# RF.net
KiCad netlist of a schematic drawn in Altium Designer
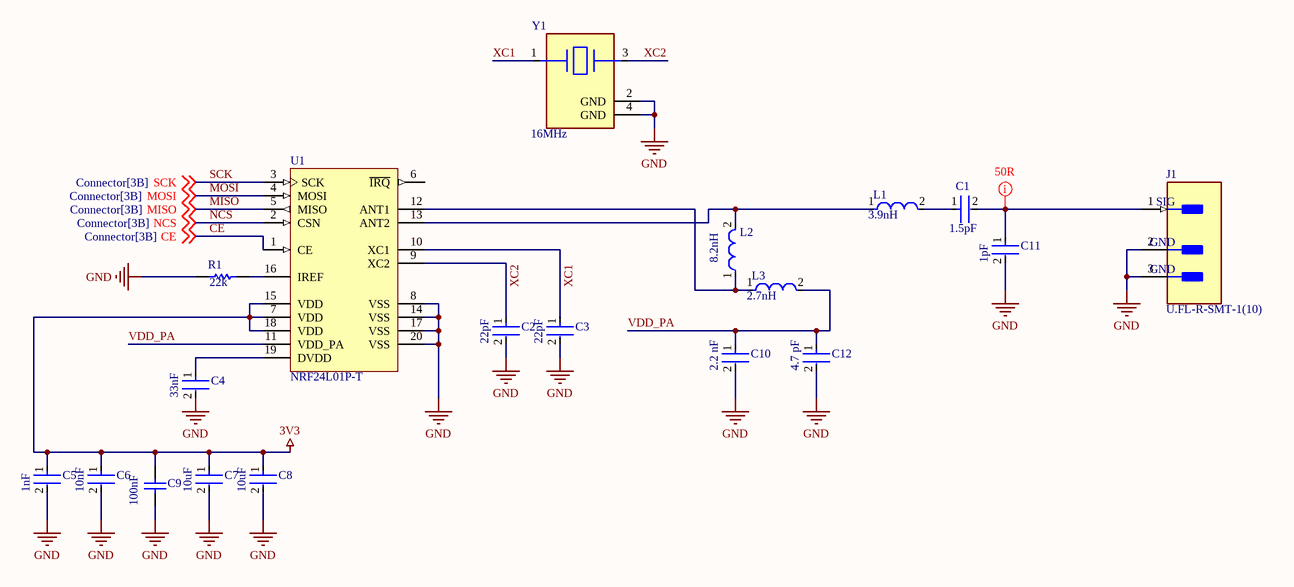
[diagram p0: RF.SchDoc]

(export (version "E")
  (design (tool "Eeschema 10.0.6"))
  (components
    (comp (ref "C1")
      (value "GCM1555C1H1R5BA16D")
      (footprint "FP-GCM155-0_05-IPC_C")
      (description "Ceramic Capacitor for Automotive 1.5pF ±0.1pF 50VDC C0G 0402 Paper T/R")
      (fields (field (name "CAPACITANCE") "1.5pF") (field (name "JLCPARTNUM") "C126500"))
      (libsource (lib "Altium Content Vault") (part "02cd4be3c70576c341d710602a673aa"))
    )
    (comp (ref "C2")
      (value "04025A220JAT2A")
      (footprint "FP-0402-L_1_0_1-W_0_5_0_1-MFG")
      (description "General Purpose Ceramic Capacitor, 0402, 22pF, 5%, C0G, 30ppm/°C, 50V")
      (fields
        (field (name "VOLTAGE") "50V")
        (field (name "TOLERANCE") "5%")
        (field (name "CAPACITANCE") "22pF")
      )
      (libsource (lib "Altium Content Vault") (part "b4654b650e69147ec39a6b967a45e02"))
    )
    (comp (ref "C3")
      (value "04025A220JAT2A")
      (footprint "FP-0402-L_1_0_1-W_0_5_0_1-MFG")
      (description "General Purpose Ceramic Capacitor, 0402, 22pF, 5%, C0G, 30ppm/°C, 50V")
      (fields
        (field (name "VOLTAGE") "50V")
        (field (name "TOLERANCE") "5%")
        (field (name "CAPACITANCE") "22pF")
      )
      (libsource (lib "Altium Content Vault") (part "b4654b650e69147ec39a6b967a45e02"))
    )
    (comp (ref "C4")
      (value "GCM155R71E333KA55D")
      (footprint "FP-GCM155-0_05-IPC_A")
      (description "Ceramic Capacitor for Automotive 33nF ±10% 25VDC X7R 0402 Paper T/R")
      (fields
        (field (name "TOLERANCE") "10%")
        (field (name "CAPACITANCE") "33nF")
        (field (name "JLCPARTNUM") "C185046")
      )
      (libsource (lib "Altium Content Vault") (part "02cd4be3c70576c341d710602a673aa"))
    )
    (comp (ref "C5")
      (value "CL05B102KB5NNNC")
      (footprint "FP-CL957-IPC_C")
      (description "Cap Ceramic 1nF 50V X7R ±10% SMD 0402 +125°C Paper T/R")
      (fields
        (field (name "TOLERANCE") "10%")
        (field (name "CAPACITANCE") "1nF")
        (field (name "VOLTAGE") "50V")
      )
      (libsource (lib "Altium Content Vault") (part "b4654b650e69147ec39a6b967a45e02"))
    )
    (comp (ref "C6")
      (value "CL05B103KB5NNNC")
      (footprint "FP-CL165-IPC_C")
      (description "Cap Ceramic 10nF 50V X7R ±10% SMD 0402 +125°C Paper T/R")
      (fields
        (field (name "VOLTAGE") "50V")
        (field (name "TOLERANCE") "10%")
        (field (name "CAPACITANCE") "10nF")
      )
      (libsource (lib "Altium Content Vault") (part "b4654b650e69147ec39a6b967a45e02"))
    )
    (comp (ref "C7")
      (value "LMK107BJ106MALTD")
      (footprint "FP-LMK107BJ106MALTD-MFG")
      (description "CAP CER 10UF 10V X5R 0603")
      (fields
        (field (name "TOLERANCE") "20%")
        (field (name "CAPACITANCE") "10uF")
        (field (name "JLCPARTNUM") "C18800")
      )
      (libsource (lib "Altium Content Vault") (part "b4654b650e69147ec39a6b967a45e02"))
    )
    (comp (ref "C8")
      (value "LMK107BJ106MALTD")
      (footprint "FP-LMK107BJ106MALTD-MFG")
      (description "CAP CER 10UF 10V X5R 0603")
      (fields
        (field (name "TOLERANCE") "20%")
        (field (name "CAPACITANCE") "10uF")
        (field (name "JLCPARTNUM") "C18800")
      )
      (libsource (lib "Altium Content Vault") (part "b4654b650e69147ec39a6b967a45e02"))
    )
    (comp (ref "C9")
      (value "100nF")
      (footprint "CAPC1050X55X23ML05T13")
      (description "Chip Capacitor, 100 nF, +/- 10%, 16 V, -55 to 125 degC, 0402 (1005 Metric), RoHS, Tape and Reel")
      (fields (field (name "MANUFACTURER") "Samsung Electro-Mechanics") (field (name "JLCPARTNUM") "C1525"))
      (libsource (lib "Altium Content Vault") (part "CAP-NP-2"))
    )
    (comp (ref "C10")
      (value "2.2 nF")
      (footprint "FP-CC0402-MFG")
      (description "CAP CER 2200PF 50V X7R 0402")
      (fields (field (name "MANUFACTURER PART NUMBER") "CC0402KRX7R9BB222") (field (name "TOLERANCE") "0.1"))
      (libsource (lib "Altium Content Vault") (part "11868f565c42a9108669ba33697ecf6"))
    )
    (comp (ref "C11")
      (value "GJM1555C1H1R0WB01D")
      (footprint "FP-GJM155-0_05-IPC_B")
      (description "Multi-Layer Ceramic Capacitor 1pF C0G  ±0.05pF 0402 Paper T/R")
      (fields
        (field (name "CAPACITANCE") "1pF")
        (field (name "VOLTAGE") "50V")
        (field (name "JLCPARTNUM") "C72134")
      )
      (libsource (lib "Altium Content Vault") (part "02cd4be3c70576c341d710602a673aa"))
    )
    (comp (ref "C12")
      (value "4.7 pF")
      (footprint "FP-AC0402-0_5-MFG")
      (description "AC0402 4.7 pF NPO 0.25% 50 V")
      (fields (field (name "TOLERANCE") "0.0025"))
      (libsource (lib "Altium Content Vault") (part "11868f565c42a9108669ba33697ecf6"))
    )
    (comp (ref "J1")
      (value "U.FL-R-SMT-1(10)")
      (footprint "FP-U_FL-R-SMT-1_10-MFG")
      (description "CONN U.FL RCPT STR 50 OHM SMD")
      (fields (field (name "JLCPARTNUM") "C88373"))
      (libsource (lib "Altium Content Vault") (part "7158abf7d987fa84906f6fb0d115710"))
    )
    (comp (ref "L1")
      (value "LQW15AN3N9B00D")
      (footprint "FP-LQW15AN_00-W0_6-0_1-MFG")
      (description "Wire Wound RF Inductor 3.9nH ±0.1nH 750mA 0.07Ω 0402 (1005)")
      (fields (field (name "INDUCTANCE") "3.9nH") (field (name "JLCPARTNUM") "C98062"))
      (libsource (lib "Altium Content Vault") (part "725321dda6339637d4d059423bc1c3c"))
    )
    (comp (ref "L2")
      (value "LQW15AN8N2G00D")
      (footprint "FP-LQW15AN_00-W0_6-0_1-MFG")
      (description "Wire Wound RF Inductor 8.2nH ±2% 540mA 0.14Ω 0402 (1005)")
      (fields
        (field (name "TOLERANCE") "2%")
        (field (name "INDUCTANCE") "8.2nH")
        (field (name "JLCPARTNUM") "C84404")
      )
      (libsource (lib "Altium Content Vault") (part "725321dda6339637d4d059423bc1c3c"))
    )
    (comp (ref "L3")
      (value "LQW15AN2N7B00D")
      (footprint "FP-LQW15AN_00-W0_6-0_1-MFG")
      (description "Wire Wound RF Inductor 2.7nH ±0.1nH 850mA 0.05Ω 0402 (1005)")
      (fields (field (name "INDUCTANCE") "2.7nH") (field (name "JLCPARTNUM") "C91239"))
      (libsource (lib "Altium Content Vault") (part "725321dda6339637d4d059423bc1c3c"))
    )
    (comp (ref "R1")
      (value "22k")
      (footprint "RESC1005X40X25NL05T10")
      (fields
        (field (name "MANUFACTURER") "Yageo / Phycomp")
        (field (name "PART NUMBER") "RC0402FR-0722KL")
        (field (name "JLCPARTNUM") "C82868")
      )
      (libsource (lib "Altium Content Vault") (part "RES"))
    )
    (comp (ref "U1")
      (value "NRF24L01P-T")
      (footprint "NRSC-QFN-20_L")
      (description "Single Chip Transceiver, 2.4 GHz, 60 mW, 1.9 to 3.6 V, -40 to 85 degC, 20-Pin QFN, RoHS, Tray")
      (fields (field (name "MANUFACTURER") "Nordic Semiconductor") (field (name "JLCPARTNUM") "C1526140"))
      (libsource (lib "Altium Content Vault") (part "NRSC-NRF24L01P-QFN-20"))
    )
    (comp (ref "Y1")
      (value "X201616MPB4SC")
      (footprint "FP-ABM11-MFG")
      (description "Crystal 16MHz ±15ppm 15pF SMD-4 2mm x 1.6mm")
      (fields
        (field (name "FREQUENCY") "16MHz")
        (field (name "TOLERANCE") "15ppm")
        (field (name "JLCPARTNUM") "C1985805")
      )
      (libsource (lib "Altium Content Vault") (part "b3c1237d77310e73098bcf11eecb25f"))
    )
  )
  (nets
    (net (code "1") (name "/VDD_PA") (class "Default")
      (node (ref "C10") (pin "1") (pinfunction "1_1") (pintype "passive"))
      (node (ref "C12") (pin "1") (pinfunction "1_1") (pintype "passive"))
      (node (ref "L3") (pin "2") (pinfunction "2_2") (pintype "passive"))
      (node (ref "U1") (pin "11") (pinfunction "VDD_PA_11") (pintype "power_in"))
    )
    (net (code "2") (name "/XC1") (class "Default")
      (node (ref "C3") (pin "1") (pinfunction "1_1") (pintype "passive"))
      (node (ref "U1") (pin "10") (pinfunction "XC1_10") (pintype "passive"))
      (node (ref "Y1") (pin "1") (pinfunction "1_1") (pintype "passive"))
    )
    (net (code "3") (name "/XC2") (class "Default")
      (node (ref "C2") (pin "1") (pinfunction "1_1") (pintype "passive"))
      (node (ref "U1") (pin "9") (pinfunction "XC2_9") (pintype "passive"))
      (node (ref "Y1") (pin "3") (pinfunction "3_3") (pintype "passive"))
    )
    (net (code "4") (name "3V3") (class "Default")
      (node (ref "C5") (pin "1") (pinfunction "1_1") (pintype "passive"))
      (node (ref "C6") (pin "1") (pinfunction "1_1") (pintype "passive"))
      (node (ref "C7") (pin "1") (pinfunction "1_1") (pintype "passive"))
      (node (ref "C8") (pin "1") (pinfunction "1_1") (pintype "passive"))
      (node (ref "C9") (pin "1") (pinfunction "1_1") (pintype "passive"))
      (node (ref "U1") (pin "15") (pinfunction "VDD_15") (pintype "power_in"))
      (node (ref "U1") (pin "18") (pinfunction "VDD_18") (pintype "power_in"))
      (node (ref "U1") (pin "7") (pinfunction "VDD_7") (pintype "power_in"))
    )
    (net (code "5") (name "CE") (class "Default")
      (node (ref "U1") (pin "1") (pinfunction "CE_1") (pintype "input"))
    )
    (net (code "6") (name "GND") (class "Default")
      (node (ref "C10") (pin "2") (pinfunction "2_2") (pintype "passive"))
      (node (ref "C11") (pin "2") (pinfunction "2_2") (pintype "passive"))
      (node (ref "C12") (pin "2") (pinfunction "2_2") (pintype "passive"))
      (node (ref "C2") (pin "2") (pinfunction "2_2") (pintype "passive"))
      (node (ref "C3") (pin "2") (pinfunction "2_2") (pintype "passive"))
      (node (ref "C4") (pin "2") (pinfunction "2_2") (pintype "passive"))
      (node (ref "C5") (pin "2") (pinfunction "2_2") (pintype "passive"))
      (node (ref "C6") (pin "2") (pinfunction "2_2") (pintype "passive"))
      (node (ref "C7") (pin "2") (pinfunction "2_2") (pintype "passive"))
      (node (ref "C8") (pin "2") (pinfunction "2_2") (pintype "passive"))
      (node (ref "C9") (pin "2") (pinfunction "2_2") (pintype "passive"))
      (node (ref "J1") (pin "2") (pinfunction "GND_2") (pintype "power_in"))
      (node (ref "J1") (pin "3") (pinfunction "GND_3") (pintype "power_in"))
      (node (ref "R1") (pin "1") (pinfunction "1_1") (pintype "passive"))
      (node (ref "U1") (pin "14") (pinfunction "VSS_14") (pintype "power_in"))
      (node (ref "U1") (pin "17") (pinfunction "VSS_17") (pintype "power_in"))
      (node (ref "U1") (pin "20") (pinfunction "VSS_20") (pintype "power_in"))
      (node (ref "U1") (pin "8") (pinfunction "VSS_8") (pintype "power_in"))
      (node (ref "Y1") (pin "2") (pinfunction "GND_2") (pintype "power_in"))
      (node (ref "Y1") (pin "4") (pinfunction "GND_4") (pintype "power_in"))
    )
    (net (code "7") (name "MISO") (class "Default")
      (node (ref "U1") (pin "5") (pinfunction "MISO_5") (pintype "output"))
    )
    (net (code "8") (name "MOSI") (class "Default")
      (node (ref "U1") (pin "4") (pinfunction "MOSI_4") (pintype "input"))
    )
    (net (code "9") (name "NCS") (class "Default")
      (node (ref "U1") (pin "2") (pinfunction "CSN_2") (pintype "input"))
    )
    (net (code "10") (name "Net-(C1-Pad1)") (class "Default")
      (node (ref "C1") (pin "1") (pinfunction "1_1") (pintype "passive"))
      (node (ref "L1") (pin "2") (pinfunction "2_2") (pintype "passive"))
    )
    (net (code "11") (name "Net-(J1-SIG)") (class "Default")
      (node (ref "C1") (pin "2") (pinfunction "2_2") (pintype "passive"))
      (node (ref "C11") (pin "1") (pinfunction "1_1") (pintype "passive"))
      (node (ref "J1") (pin "1") (pinfunction "SIG_1") (pintype "input"))
    )
    (net (code "12") (name "Net-(U1-ANT1)") (class "Default")
      (node (ref "L2") (pin "1") (pinfunction "1_1") (pintype "passive"))
      (node (ref "L3") (pin "1") (pinfunction "1_1") (pintype "passive"))
      (node (ref "U1") (pin "12") (pinfunction "ANT1_12") (pintype "passive"))
    )
    (net (code "13") (name "Net-(U1-ANT2)") (class "Default")
      (node (ref "L1") (pin "1") (pinfunction "1_1") (pintype "passive"))
      (node (ref "L2") (pin "2") (pinfunction "2_2") (pintype "passive"))
      (node (ref "U1") (pin "13") (pinfunction "ANT2_13") (pintype "passive"))
    )
    (net (code "14") (name "Net-(U1-DVDD)") (class "Default")
      (node (ref "C4") (pin "1") (pinfunction "1_1") (pintype "passive"))
      (node (ref "U1") (pin "19") (pinfunction "DVDD_19") (pintype "power_in"))
    )
    (net (code "15") (name "Net-(U1-IREF)") (class "Default")
      (node (ref "R1") (pin "2") (pinfunction "2_2") (pintype "passive"))
      (node (ref "U1") (pin "16") (pinfunction "IREF_16") (pintype "passive"))
    )
    (net (code "16") (name "SCK") (class "Default")
      (node (ref "U1") (pin "3") (pinfunction "SCK_3") (pintype "input"))
    )
    (net (code "17") (name "unconnected-(U1-~{IRQ}-Pad6)") (class "Default")
      (node (ref "U1") (pin "6") (pinfunction "~{IRQ}_6") (pintype "output"))
    )
  )
)
